# Sheet1.net
KiCad netlist of a schematic drawn in Altium Designer
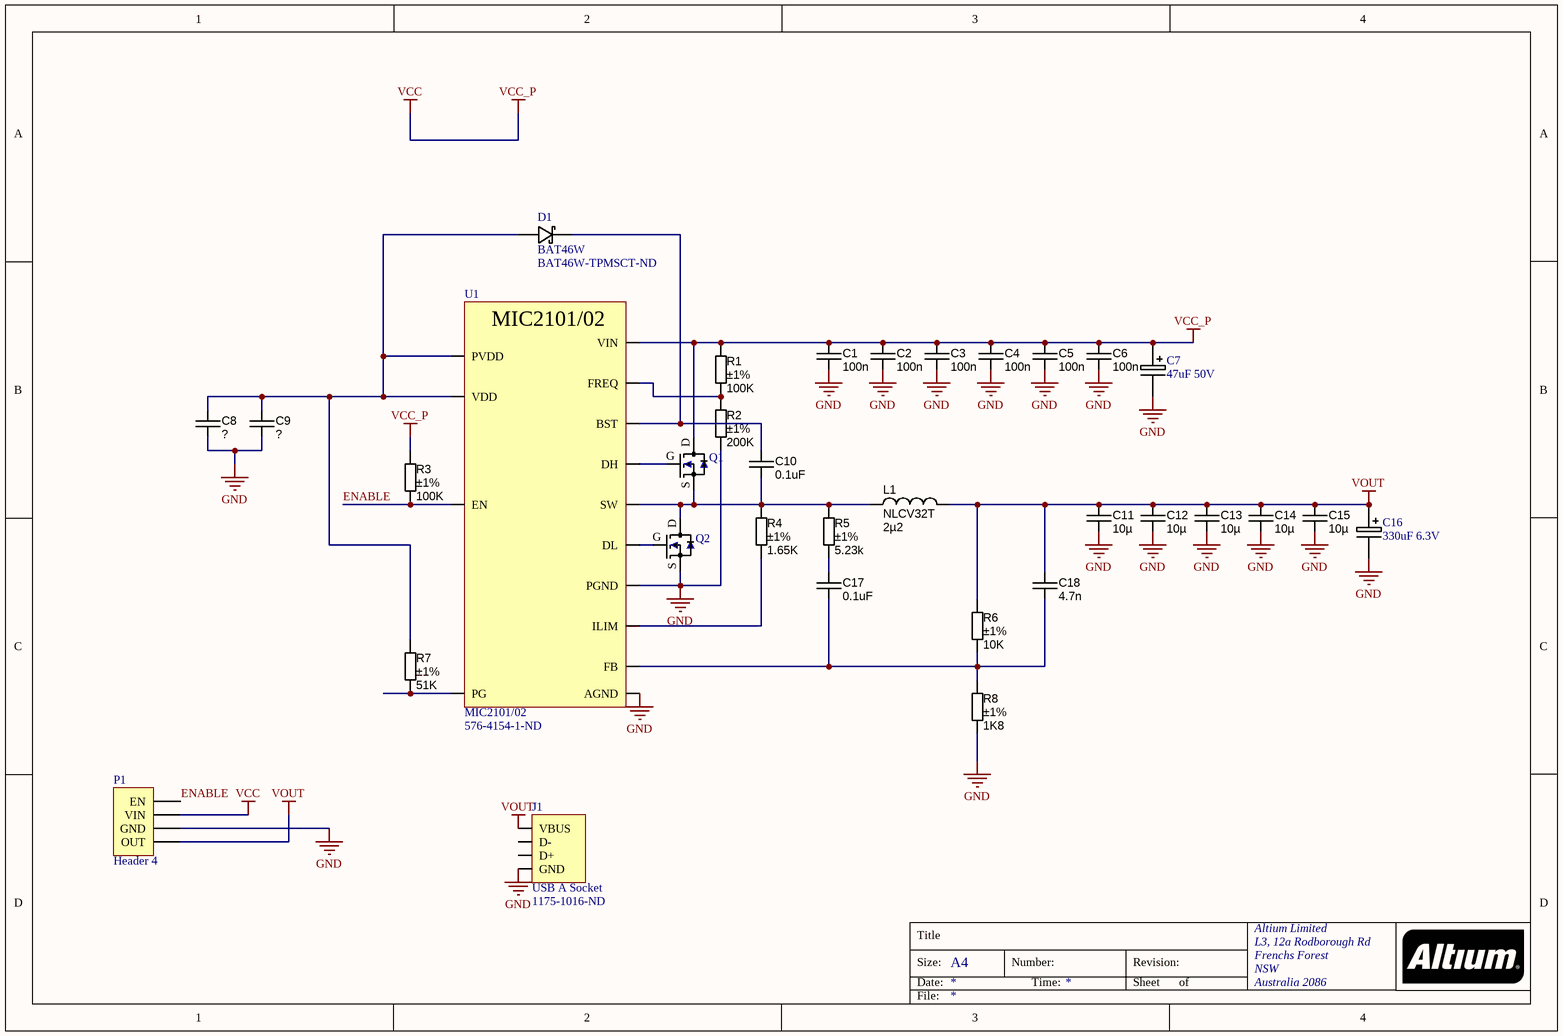
[diagram p0: Sheet1.SchDoc]

(export (version "E")
  (design (tool "Eeschema 10.0.6"))
  (components
    (comp (ref "C1")
      (value "100n")
      (footprint "CAPC1608X90N")
      (description "Capacitor SMD Cer 100nF 10% 50V X7R 0603")
      (fields (field (name "TOLERANCE") "±10%") (field (name "Comment") "approved sub OK"))
      (libsource (lib "PBL - Capacitors") (part "CAPC_100n_0603_X7R_50V_10%"))
    )
    (comp (ref "C2")
      (value "100n")
      (footprint "CAPC1608X90N")
      (description "Capacitor SMD Cer 100nF 10% 50V X7R 0603")
      (fields (field (name "TOLERANCE") "±10%") (field (name "Comment") "approved sub OK"))
      (libsource (lib "PBL - Capacitors") (part "CAPC_100n_0603_X7R_50V_10%"))
    )
    (comp (ref "C3")
      (value "100n")
      (footprint "CAPC1608X90N")
      (description "Capacitor SMD Cer 100nF 10% 50V X7R 0603")
      (fields (field (name "TOLERANCE") "±10%") (field (name "Comment") "approved sub OK"))
      (libsource (lib "PBL - Capacitors") (part "CAPC_100n_0603_X7R_50V_10%"))
    )
    (comp (ref "C4")
      (value "100n")
      (footprint "CAPC1608X90N")
      (description "Capacitor SMD Cer 100nF 10% 50V X7R 0603")
      (fields (field (name "TOLERANCE") "±10%") (field (name "Comment") "approved sub OK"))
      (libsource (lib "PBL - Capacitors") (part "CAPC_100n_0603_X7R_50V_10%"))
    )
    (comp (ref "C5")
      (value "100n")
      (footprint "CAPC1608X90N")
      (description "Capacitor SMD Cer 100nF 10% 50V X7R 0603")
      (fields (field (name "TOLERANCE") "±10%") (field (name "Comment") "approved sub OK"))
      (libsource (lib "PBL - Capacitors") (part "CAPC_100n_0603_X7R_50V_10%"))
    )
    (comp (ref "C6")
      (value "100n")
      (footprint "CAPC1608X90N")
      (description "Capacitor SMD Cer 100nF 10% 50V X7R 0603")
      (fields (field (name "TOLERANCE") "±10%") (field (name "Comment") "approved sub OK"))
      (libsource (lib "PBL - Capacitors") (part "CAPC_100n_0603_X7R_50V_10%"))
    )
    (comp (ref "C7")
      (value "47uF 50V")
      (footprint "Capacitor Panasonic FTV-D")
      (libsource (lib "Schlib1") (part "CAPE 47uF 50V"))
    )
    (comp (ref "C8")
      (value "?")
      (footprint "CAPC1608X90N")
      (description "Capacitor SMD Cer 1nF 10% 100V X7R 0603")
      (fields (field (name "TOLERANCE") "±10%") (field (name "Comment") "approved sub OK"))
      (libsource (lib "PBL - Capacitors") (part "CAPC_1n_0603_X7R_100V_10%"))
    )
    (comp (ref "C9")
      (value "?")
      (footprint "CAPC1608X90N")
      (description "Capacitor SMD Cer 1nF 10% 100V X7R 0603")
      (fields (field (name "TOLERANCE") "±10%") (field (name "Comment") "approved sub OK"))
      (libsource (lib "PBL - Capacitors") (part "CAPC_1n_0603_X7R_100V_10%"))
    )
    (comp (ref "C10")
      (value "0.1uF")
      (footprint "CAPC1608X90N")
      (description "Capacitor SMD Cer 1nF 10% 100V X7R 0603")
      (fields (field (name "TOLERANCE") "±10%") (field (name "Comment") "approved sub OK"))
      (libsource (lib "PBL - Capacitors") (part "CAPC_1n_0603_X7R_100V_10%"))
    )
    (comp (ref "C11")
      (value "10µ")
      (footprint "CAPC2012X135N")
      (description "Capacitor SMD Cer 10uF 10% 10V X5R 0805")
      (fields (field (name "TOLERANCE") "±10%") (field (name "Comment") "approved sub OK"))
      (libsource (lib "PBL - Capacitors") (part "CAPC_10u_0805_10V"))
    )
    (comp (ref "C12")
      (value "10µ")
      (footprint "CAPC2012X135N")
      (description "Capacitor SMD Cer 10uF 10% 10V X5R 0805")
      (fields (field (name "TOLERANCE") "±10%") (field (name "Comment") "approved sub OK"))
      (libsource (lib "PBL - Capacitors") (part "CAPC_10u_0805_10V"))
    )
    (comp (ref "C13")
      (value "10µ")
      (footprint "CAPC2012X135N")
      (description "Capacitor SMD Cer 10uF 10% 10V X5R 0805")
      (fields (field (name "TOLERANCE") "±10%") (field (name "Comment") "approved sub OK"))
      (libsource (lib "PBL - Capacitors") (part "CAPC_10u_0805_10V"))
    )
    (comp (ref "C14")
      (value "10µ")
      (footprint "CAPC2012X135N")
      (description "Capacitor SMD Cer 10uF 10% 10V X5R 0805")
      (fields (field (name "TOLERANCE") "±10%") (field (name "Comment") "approved sub OK"))
      (libsource (lib "PBL - Capacitors") (part "CAPC_10u_0805_10V"))
    )
    (comp (ref "C15")
      (value "10µ")
      (footprint "CAPC2012X135N")
      (description "Capacitor SMD Cer 10uF 10% 10V X5R 0805")
      (fields (field (name "TOLERANCE") "±10%") (field (name "Comment") "approved sub OK"))
      (libsource (lib "PBL - Capacitors") (part "CAPC_10u_0805_10V"))
    )
    (comp (ref "C16")
      (value "330uF 6.3V")
      (footprint "Capacitor Panasonic FTV-D")
      (libsource (lib "Schlib1") (part "CAPE 330uF 6.3V UUD0J221MCL1GS_1"))
    )
    (comp (ref "C17")
      (value "0.1uF")
      (footprint "CAPC1608X90N")
      (description "Capacitor SMD Cer 1nF 10% 100V X7R 0603")
      (fields (field (name "TOLERANCE") "±10%") (field (name "Comment") "approved sub OK"))
      (libsource (lib "PBL - Capacitors") (part "CAPC_1n_0603_X7R_100V_10%"))
    )
    (comp (ref "C18")
      (value "4.7n")
      (footprint "CAPC1608X90N")
      (description "Capacitor SMD Cer 47nF 10% 50V X7R 0603")
      (fields (field (name "TOLERANCE") "±10%"))
      (libsource (lib "PBL - Capacitors") (part "CAPC_47n_0603_X7R_50V_10%"))
    )
    (comp (ref "D1")
      (value "BAT46W")
      (footprint "BAT46W")
      (fields (field (name "SUPPLIER PART NUMBER 1") "BAT46W-TPMSCT-ND"))
      (libsource (lib "Schlib1") (part "BAT46W"))
    )
    (comp (ref "J1")
      (value "USB A Socket")
      (footprint "USB A Socket - 1002-002-01100")
      (fields (field (name "SUPPLIER PART NUMBER 1") "1175-1016-ND"))
      (libsource (lib "Schlib1") (part "USB A Socket"))
    )
    (comp (ref "L1")
      (value "NLCV32T")
      (footprint "INDM3225X240N")
      (description "Inductor 2.2uH 1.2A 1210 SMD chip")
      (fields (field (name "TOLERANCE") "±20%") (field (name "ALTIUM_VALUE") "2µ2"))
      (libsource (lib "PBL - Inductors") (part "INDC_2u2_1210_1200mA"))
    )
    (comp (ref "P1")
      (value "Header 4")
      (footprint "HDR1X4")
      (description "Header, 4-Pin")
      (fields (field (name "PUBLISHER") "Altium Limited"))
      (libsource (lib "Miscellaneous Connectors") (part "Header 4"))
    )
    (comp (ref "Q1")
      (value "MOSFET N-CH 30V 6A 4.5V Drive SSM3K333R")
      (footprint "SSM3K333R")
      (libsource (lib "Schlib1") (part "MOSFET N-CH 30V 6A 4.5V Drive SSM3K333R"))
    )
    (comp (ref "Q2")
      (value "MOSFET N-CH 30V 6A 4.5V Drive SSM3K333R")
      (footprint "SSM3K333R")
      (libsource (lib "Schlib1") (part "MOSFET N-CH 30V 6A 4.5V Drive SSM3K333R"))
    )
    (comp (ref "R1")
      (value "100K")
      (footprint "RESC1608X55N")
      (description "Resistor SMD chip 100k Ohm 0.1W 1% 0603")
      (fields (field (name "TOLERANCE") "±1%") (field (name "Comment") "Thick Film"))
      (libsource (lib "PBL - Resistors") (part "RES_100K_0603_1%"))
    )
    (comp (ref "R2")
      (value "200K")
      (footprint "RESC1608X55N")
      (description "Resistor SMD chip 100k Ohm 0.1W 1% 0603")
      (fields (field (name "TOLERANCE") "±1%") (field (name "Comment") "Thick Film"))
      (libsource (lib "PBL - Resistors") (part "RES_100K_0603_1%"))
    )
    (comp (ref "R3")
      (value "100K")
      (footprint "RESC1608X55N")
      (description "Resistor SMD chip 100k Ohm 0.1W 1% 0603")
      (fields (field (name "TOLERANCE") "±1%") (field (name "Comment") "Thick Film"))
      (libsource (lib "PBL - Resistors") (part "RES_100K_0603_1%"))
    )
    (comp (ref "R4")
      (value "1.65K")
      (footprint "RESC1608X55N")
      (description "Resistor SMD chip 100k Ohm 0.1W 1% 0603")
      (fields (field (name "TOLERANCE") "±1%") (field (name "Comment") "Thick Film"))
      (libsource (lib "PBL - Resistors") (part "RES_100K_0603_1%"))
    )
    (comp (ref "R5")
      (value "5.23k")
      (footprint "RESC1608X55N")
      (description "Resistor SMD chip 100k Ohm 0.1W 1% 0603")
      (fields (field (name "TOLERANCE") "±1%") (field (name "Comment") "Thick Film"))
      (libsource (lib "PBL - Resistors") (part "RES_100K_0603_1%"))
    )
    (comp (ref "R6")
      (value "10K")
      (footprint "RESC1608X55N")
      (description "Resistor SMD chip 10k Ohm 0.1W 1% 0603")
      (fields (field (name "TOLERANCE") "±1%") (field (name "Comment") "Thick Film"))
      (libsource (lib "PBL - Resistors") (part "RES_10K_0603_1%"))
    )
    (comp (ref "R7")
      (value "51K")
      (footprint "RESC1608X55N")
      (description "Resistor SMD chip 51k Ohm 0.1W 1% 0603")
      (fields (field (name "TOLERANCE") "±1%") (field (name "Comment") "Thick Film"))
      (libsource (lib "PBL - Resistors") (part "RES_51K_0603_1%"))
    )
    (comp (ref "R8")
      (value "1K8")
      (footprint "RESC2012X70N")
      (description "Resistor SMD chip 1.8k Ohm 0.125W 1% 0805")
      (fields (field (name "TOLERANCE") "±1%") (field (name "Comment") "Thick Film"))
      (libsource (lib "PBL - Resistors") (part "RES_1K8_0805_1%"))
    )
    (comp (ref "U1")
      (value "MIC2101/02")
      (footprint "QFN50P300X300X90_HS-17N")
      (fields (field (name "SUPPLIER PART NUMBER 1") "576-4154-1-ND"))
      (libsource (lib "Schlib1") (part "MIC2101/02"))
    )
  )
  (nets
    (net (code "1") (name "/ENABLE") (class "Default")
      (node (ref "P1") (pin "1") (pinfunction "EN_1") (pintype "passive"))
      (node (ref "R3") (pin "2") (pinfunction "2_2") (pintype "passive"))
      (node (ref "U1") (pin "15") (pinfunction "EN_15") (pintype "passive"))
    )
    (net (code "2") (name "GND") (class "Default")
      (node (ref "C1") (pin "2") (pintype "passive"))
      (node (ref "C11") (pin "2") (pintype "passive"))
      (node (ref "C12") (pin "2") (pintype "passive"))
      (node (ref "C13") (pin "2") (pintype "passive"))
      (node (ref "C14") (pin "2") (pintype "passive"))
      (node (ref "C15") (pin "2") (pintype "passive"))
      (node (ref "C16") (pin "-") (pintype "passive"))
      (node (ref "C2") (pin "2") (pintype "passive"))
      (node (ref "C3") (pin "2") (pintype "passive"))
      (node (ref "C4") (pin "2") (pintype "passive"))
      (node (ref "C5") (pin "2") (pintype "passive"))
      (node (ref "C6") (pin "2") (pintype "passive"))
      (node (ref "C7") (pin "-") (pintype "passive"))
      (node (ref "C8") (pin "2") (pintype "passive"))
      (node (ref "C9") (pin "2") (pintype "passive"))
      (node (ref "J1") (pin "4") (pinfunction "GND_4") (pintype "passive"))
      (node (ref "P1") (pin "3") (pinfunction "GND_3") (pintype "passive"))
      (node (ref "Q2") (pin "S") (pinfunction "3_S") (pintype "passive"))
      (node (ref "R2") (pin "2") (pinfunction "2_2") (pintype "passive"))
      (node (ref "R8") (pin "2") (pinfunction "2_2") (pintype "passive"))
      (node (ref "U1") (pin "12") (pinfunction "AGND_12") (pintype "passive"))
      (node (ref "U1") (pin "5") (pinfunction "PGND_5") (pintype "passive"))
    )
    (net (code "3") (name "Net-(C17-Pad1)") (class "Default")
      (node (ref "C17") (pin "1") (pintype "passive"))
      (node (ref "R5") (pin "2") (pinfunction "2_2") (pintype "passive"))
    )
    (net (code "4") (name "Net-(Q1-3)") (class "Default")
      (node (ref "C10") (pin "2") (pintype "passive"))
      (node (ref "L1") (pin "1") (pinfunction "1_1") (pintype "passive"))
      (node (ref "Q1") (pin "S") (pinfunction "3_S") (pintype "passive"))
      (node (ref "Q2") (pin "D") (pinfunction "D_D") (pintype "passive"))
      (node (ref "R4") (pin "1") (pinfunction "1_1") (pintype "passive"))
      (node (ref "R5") (pin "1") (pinfunction "1_1") (pintype "passive"))
      (node (ref "U1") (pin "8") (pinfunction "SW_8") (pintype "passive"))
    )
    (net (code "5") (name "Net-(U1-BST)") (class "Default")
      (node (ref "C10") (pin "1") (pintype "passive"))
      (node (ref "D1") (pin "K") (pinfunction "K_K") (pintype "passive"))
      (node (ref "U1") (pin "10") (pinfunction "BST_10") (pintype "passive"))
    )
    (net (code "6") (name "Net-(U1-DH)") (class "Default")
      (node (ref "Q1") (pin "G") (pinfunction "G_G") (pintype "passive"))
      (node (ref "U1") (pin "7") (pinfunction "DH_7") (pintype "passive"))
    )
    (net (code "7") (name "Net-(U1-DL)") (class "Default")
      (node (ref "Q2") (pin "G") (pinfunction "G_G") (pintype "passive"))
      (node (ref "U1") (pin "4") (pinfunction "DL_4") (pintype "passive"))
    )
    (net (code "8") (name "Net-(U1-FB)") (class "Default")
      (node (ref "C17") (pin "2") (pintype "passive"))
      (node (ref "C18") (pin "2") (pintype "passive"))
      (node (ref "R6") (pin "2") (pinfunction "2_2") (pintype "passive"))
      (node (ref "R8") (pin "1") (pinfunction "1_1") (pintype "passive"))
      (node (ref "U1") (pin "13") (pinfunction "FB_13") (pintype "passive"))
    )
    (net (code "9") (name "Net-(U1-FREQ)") (class "Default")
      (node (ref "R1") (pin "2") (pinfunction "2_2") (pintype "passive"))
      (node (ref "R2") (pin "1") (pinfunction "1_1") (pintype "passive"))
      (node (ref "U1") (pin "6") (pinfunction "FREQ_6") (pintype "passive"))
    )
    (net (code "10") (name "Net-(U1-ILIM)") (class "Default")
      (node (ref "R4") (pin "2") (pinfunction "2_2") (pintype "passive"))
      (node (ref "U1") (pin "3") (pinfunction "ILIM_3") (pintype "passive"))
    )
    (net (code "11") (name "Net-(U1-PG)") (class "Default")
      (node (ref "R7") (pin "2") (pinfunction "2_2") (pintype "passive"))
      (node (ref "U1") (pin "14") (pinfunction "PG_14") (pintype "passive"))
    )
    (net (code "12") (name "Net-(U1-PVDD)") (class "Default")
      (node (ref "C8") (pin "1") (pintype "passive"))
      (node (ref "C9") (pin "1") (pintype "passive"))
      (node (ref "D1") (pin "A") (pinfunction "A_A") (pintype "passive"))
      (node (ref "R7") (pin "1") (pinfunction "1_1") (pintype "passive"))
      (node (ref "U1") (pin "1") (pinfunction "VDD_1") (pintype "passive"))
      (node (ref "U1") (pin "2") (pinfunction "PVDD_2") (pintype "passive"))
    )
    (net (code "13") (name "VCC") (class "Default")
      (node (ref "C1") (pin "1") (pintype "passive"))
      (node (ref "C2") (pin "1") (pintype "passive"))
      (node (ref "C3") (pin "1") (pintype "passive"))
      (node (ref "C4") (pin "1") (pintype "passive"))
      (node (ref "C5") (pin "1") (pintype "passive"))
      (node (ref "C6") (pin "1") (pintype "passive"))
      (node (ref "C7") (pin "+") (pintype "passive"))
      (node (ref "P1") (pin "2") (pinfunction "VIN_2") (pintype "passive"))
      (node (ref "Q1") (pin "D") (pinfunction "D_D") (pintype "passive"))
      (node (ref "R1") (pin "1") (pinfunction "1_1") (pintype "passive"))
      (node (ref "R3") (pin "1") (pinfunction "1_1") (pintype "passive"))
      (node (ref "U1") (pin "16") (pinfunction "VIN_16") (pintype "passive"))
    )
    (net (code "14") (name "VOUT") (class "Default")
      (node (ref "C11") (pin "1") (pintype "passive"))
      (node (ref "C12") (pin "1") (pintype "passive"))
      (node (ref "C13") (pin "1") (pintype "passive"))
      (node (ref "C14") (pin "1") (pintype "passive"))
      (node (ref "C15") (pin "1") (pintype "passive"))
      (node (ref "C16") (pin "+") (pintype "passive"))
      (node (ref "C18") (pin "1") (pintype "passive"))
      (node (ref "J1") (pin "1") (pinfunction "VBUS_1") (pintype "passive"))
      (node (ref "L1") (pin "2") (pinfunction "2_2") (pintype "passive"))
      (node (ref "P1") (pin "4") (pinfunction "OUT_4") (pintype "passive"))
      (node (ref "R6") (pin "1") (pinfunction "1_1") (pintype "passive"))
    )
    (net (code "15") (name "unconnected-(J1-D+-Pad3)") (class "Default")
      (node (ref "J1") (pin "3") (pinfunction "D+_3") (pintype "passive"))
    )
    (net (code "16") (name "unconnected-(J1-D--Pad2)") (class "Default")
      (node (ref "J1") (pin "2") (pinfunction "D-_2") (pintype "passive"))
    )
  )
)
